# ankle_sch.net
KiCad netlist of a schematic drawn in Altium Designer
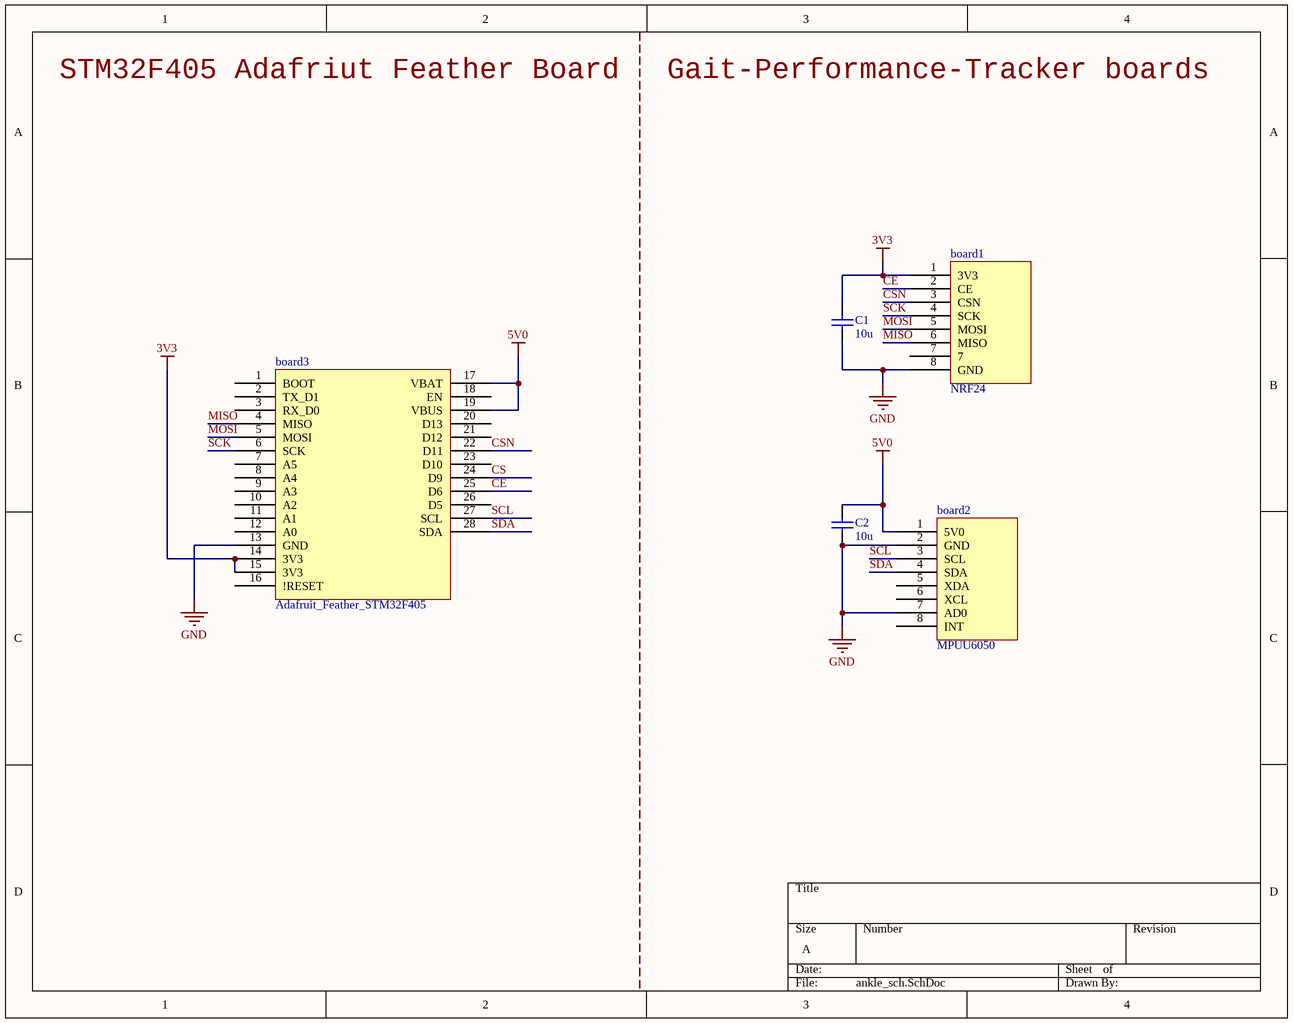
[diagram p0: ankle_sch.SchDoc]

(export (version "E")
  (design (tool "Eeschema 10.0.6"))
  (components
    (comp (ref "board1") (value "NRF24") (footprint "nrf24") (libsource (lib "Schlib1") (part "NRF24")))
    (comp (ref "board2")
      (value "MPUU6050")
      (footprint "mpu6050")
      (libsource (lib "Schlib1") (part "MPUU6050"))
    )
    (comp (ref "board3")
      (value "Adafruit_Feather_STM32F405")
      (footprint "Adafruit_Feather_STM32F405")
      (libsource (lib "Schlib1") (part "Adafruit_Feather_STM32F405"))
    )
    (comp (ref "C1")
      (value "10u")
      (description "Capacitor")
      (libsource (lib "Simulation Generic Components") (part "Capacitor"))
    )
    (comp (ref "C2")
      (value "10u")
      (description "Capacitor")
      (libsource (lib "Simulation Generic Components") (part "Capacitor"))
    )
  )
  (nets
    (net (code "1") (name "/CE") (class "Default")
      (node (ref "board1") (pin "2") (pinfunction "CE_2") (pintype "passive"))
      (node (ref "board3") (pin "25") (pinfunction "D6_25") (pintype "passive"))
    )
    (net (code "2") (name "/CS") (class "Default")
      (node (ref "board3") (pin "24") (pinfunction "D9_24") (pintype "passive"))
    )
    (net (code "3") (name "/CSN") (class "Default")
      (node (ref "board1") (pin "3") (pinfunction "CSN_3") (pintype "passive"))
      (node (ref "board3") (pin "22") (pinfunction "D11_22") (pintype "passive"))
    )
    (net (code "4") (name "/MISO") (class "Default")
      (node (ref "board1") (pin "6") (pinfunction "MISO_6") (pintype "passive"))
      (node (ref "board3") (pin "4") (pinfunction "MISO_4") (pintype "passive"))
    )
    (net (code "5") (name "/MOSI") (class "Default")
      (node (ref "board1") (pin "5") (pinfunction "MOSI_5") (pintype "passive"))
      (node (ref "board3") (pin "5") (pinfunction "MOSI_5") (pintype "passive"))
    )
    (net (code "6") (name "/SCK") (class "Default")
      (node (ref "board1") (pin "4") (pinfunction "SCK_4") (pintype "passive"))
      (node (ref "board3") (pin "6") (pinfunction "SCK_6") (pintype "passive"))
    )
    (net (code "7") (name "/SCL") (class "Default")
      (node (ref "board2") (pin "3") (pinfunction "SCL_3") (pintype "passive"))
      (node (ref "board3") (pin "27") (pinfunction "SCL_27") (pintype "passive"))
    )
    (net (code "8") (name "/SDA") (class "Default")
      (node (ref "board2") (pin "4") (pinfunction "SDA_4") (pintype "passive"))
      (node (ref "board3") (pin "28") (pinfunction "SDA_28") (pintype "passive"))
    )
    (net (code "9") (name "3V3") (class "Default")
      (node (ref "C1") (pin "2") (pinfunction "2_2") (pintype "passive"))
      (node (ref "board1") (pin "1") (pinfunction "3V3_1") (pintype "passive"))
      (node (ref "board3") (pin "14") (pinfunction "3V3_14") (pintype "passive"))
      (node (ref "board3") (pin "15") (pinfunction "3V3_15") (pintype "passive"))
    )
    (net (code "10") (name "5V0") (class "Default")
      (node (ref "C2") (pin "2") (pinfunction "2_2") (pintype "passive"))
      (node (ref "board2") (pin "1") (pinfunction "5V0_1") (pintype "passive"))
      (node (ref "board3") (pin "17") (pinfunction "VBAT_17") (pintype "passive"))
      (node (ref "board3") (pin "19") (pinfunction "VBUS_19") (pintype "passive"))
    )
    (net (code "11") (name "GND") (class "Default")
      (node (ref "C1") (pin "1") (pinfunction "1_1") (pintype "passive"))
      (node (ref "C2") (pin "1") (pinfunction "1_1") (pintype "passive"))
      (node (ref "board1") (pin "8") (pinfunction "GND_8") (pintype "passive"))
      (node (ref "board2") (pin "2") (pinfunction "GND_2") (pintype "passive"))
      (node (ref "board2") (pin "7") (pinfunction "AD0_7") (pintype "passive"))
      (node (ref "board3") (pin "13") (pinfunction "GND_13") (pintype "passive"))
    )
    (net (code "12") (name "unconnected-(board1-Pad7)") (class "Default")
      (node (ref "board1") (pin "7") (pinfunction "7_7") (pintype "passive"))
    )
    (net (code "13") (name "unconnected-(board2-INT-Pad8)") (class "Default")
      (node (ref "board2") (pin "8") (pinfunction "INT_8") (pintype "passive"))
    )
    (net (code "14") (name "unconnected-(board2-XCL-Pad6)") (class "Default")
      (node (ref "board2") (pin "6") (pinfunction "XCL_6") (pintype "passive"))
    )
    (net (code "15") (name "unconnected-(board2-XDA-Pad5)") (class "Default")
      (node (ref "board2") (pin "5") (pinfunction "XDA_5") (pintype "passive"))
    )
    (net (code "16") (name "unconnected-(board3-!RESET-Pad16)") (class "Default")
      (node (ref "board3") (pin "16") (pinfunction "!RESET_16") (pintype "passive"))
    )
    (net (code "17") (name "unconnected-(board3-A0-Pad12)") (class "Default")
      (node (ref "board3") (pin "12") (pinfunction "A0_12") (pintype "passive"))
    )
    (net (code "18") (name "unconnected-(board3-A1-Pad11)") (class "Default")
      (node (ref "board3") (pin "11") (pinfunction "A1_11") (pintype "passive"))
    )
    (net (code "19") (name "unconnected-(board3-A2-Pad10)") (class "Default")
      (node (ref "board3") (pin "10") (pinfunction "A2_10") (pintype "passive"))
    )
    (net (code "20") (name "unconnected-(board3-A3-Pad9)") (class "Default")
      (node (ref "board3") (pin "9") (pinfunction "A3_9") (pintype "passive"))
    )
    (net (code "21") (name "unconnected-(board3-A4-Pad8)") (class "Default")
      (node (ref "board3") (pin "8") (pinfunction "A4_8") (pintype "passive"))
    )
    (net (code "22") (name "unconnected-(board3-A5-Pad7)") (class "Default")
      (node (ref "board3") (pin "7") (pinfunction "A5_7") (pintype "passive"))
    )
    (net (code "23") (name "unconnected-(board3-BOOT-Pad1)") (class "Default")
      (node (ref "board3") (pin "1") (pinfunction "BOOT_1") (pintype "passive"))
    )
    (net (code "24") (name "unconnected-(board3-D5-Pad26)") (class "Default")
      (node (ref "board3") (pin "26") (pinfunction "D5_26") (pintype "passive"))
    )
    (net (code "25") (name "unconnected-(board3-D10-Pad23)") (class "Default")
      (node (ref "board3") (pin "23") (pinfunction "D10_23") (pintype "passive"))
    )
    (net (code "26") (name "unconnected-(board3-D12-Pad21)") (class "Default")
      (node (ref "board3") (pin "21") (pinfunction "D12_21") (pintype "passive"))
    )
    (net (code "27") (name "unconnected-(board3-D13-Pad20)") (class "Default")
      (node (ref "board3") (pin "20") (pinfunction "D13_20") (pintype "passive"))
    )
    (net (code "28") (name "unconnected-(board3-EN-Pad18)") (class "Default")
      (node (ref "board3") (pin "18") (pinfunction "EN_18") (pintype "passive"))
    )
    (net (code "29") (name "unconnected-(board3-RX_D0-Pad3)") (class "Default")
      (node (ref "board3") (pin "3") (pinfunction "RX_D0_3") (pintype "passive"))
    )
    (net (code "30") (name "unconnected-(board3-TX_D1-Pad2)") (class "Default")
      (node (ref "board3") (pin "2") (pinfunction "TX_D1_2") (pintype "passive"))
    )
  )
)
